# fmc_digital_io_fmc_connector.net
KiCad netlist of a schematic drawn in Altium Designer
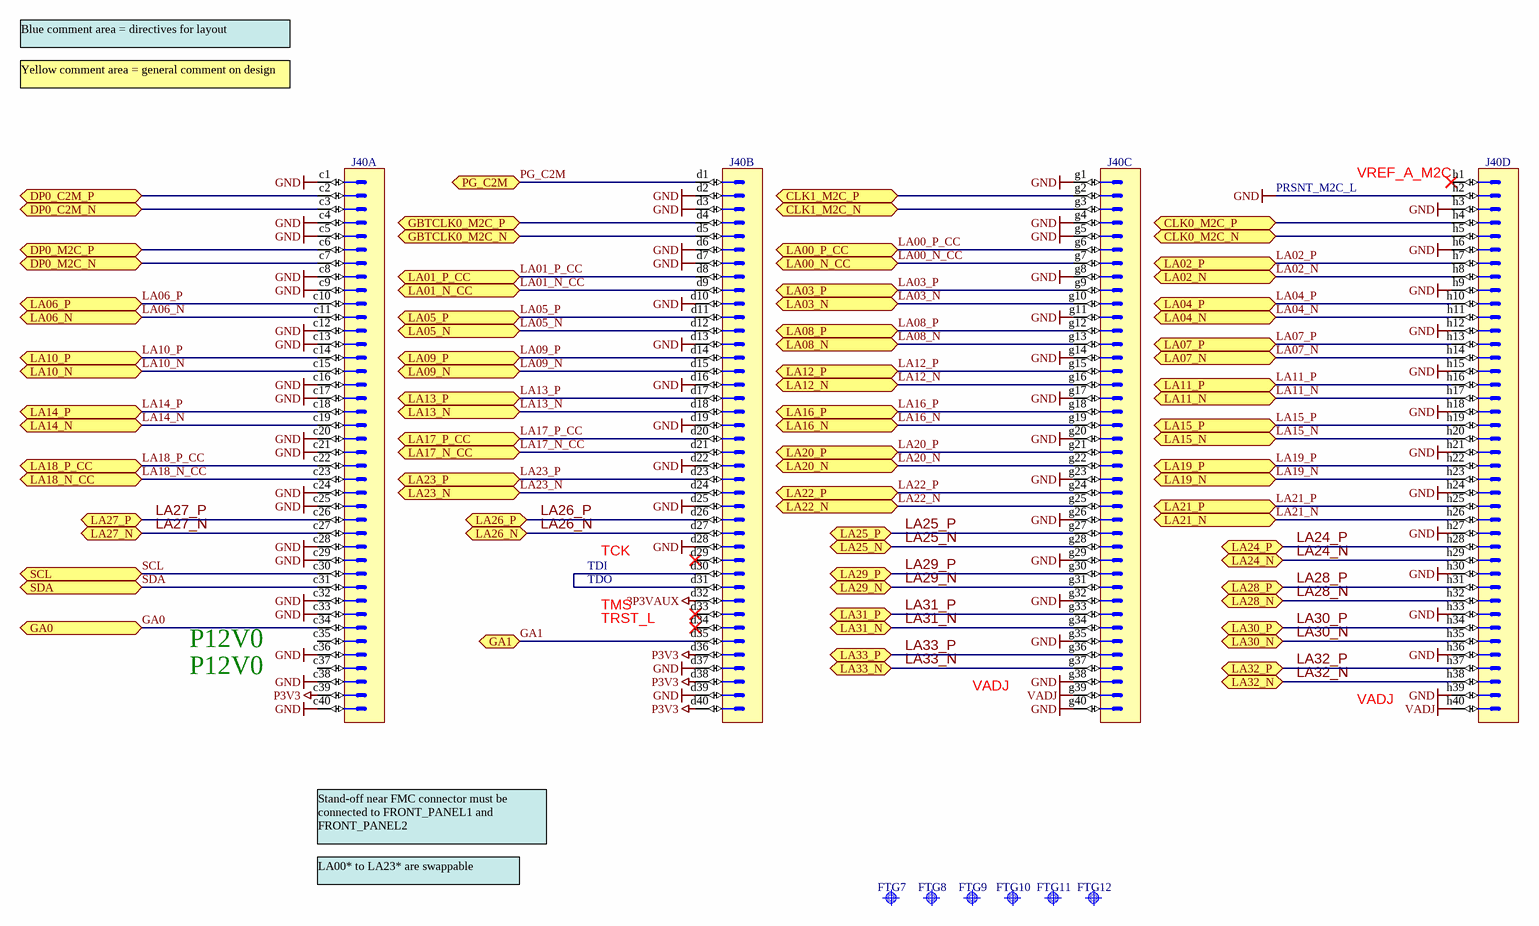
[diagram p0: fmc_digital_io_fmc_connector.SchDoc]

(export (version "E")
  (design (tool "Eeschema 10.0.6"))
  (components
    (comp (ref "FTG7")
      (value "Use only in PCB")
      (footprint "FIDUCIAL_TOP_S100-200")
      (description "Fiducial Target")
      (fields (field (name "PART NUMBER") "FIDUCIAL_TARGET_S100-200") (field (name "AUTHOR") "CERN DEM JLC"))
      (libsource (lib "Eletro-mechanical") (part "Fiducial Target"))
    )
    (comp (ref "FTG8")
      (value "Use only in PCB")
      (footprint "FIDUCIAL_TOP_S100-200")
      (description "Fiducial Target")
      (fields (field (name "PART NUMBER") "FIDUCIAL_TARGET_S100-200") (field (name "AUTHOR") "CERN DEM JLC"))
      (libsource (lib "Eletro-mechanical") (part "Fiducial Target"))
    )
    (comp (ref "FTG9")
      (value "Use only in PCB")
      (footprint "FIDUCIAL_TOP_S100-200")
      (description "Fiducial Target")
      (fields (field (name "PART NUMBER") "FIDUCIAL_TARGET_S100-200") (field (name "AUTHOR") "CERN DEM JLC"))
      (libsource (lib "Eletro-mechanical") (part "Fiducial Target"))
    )
    (comp (ref "FTG10")
      (value "Use only in PCB")
      (footprint "FIDUCIAL_TOP_S100-200")
      (description "Fiducial Target")
      (fields (field (name "PART NUMBER") "FIDUCIAL_TARGET_S100-200") (field (name "AUTHOR") "CERN DEM JLC"))
      (libsource (lib "Eletro-mechanical") (part "Fiducial Target"))
    )
    (comp (ref "FTG11")
      (value "Use only in PCB")
      (footprint "FIDUCIAL_TOP_S100-200")
      (description "Fiducial Target")
      (fields (field (name "PART NUMBER") "FIDUCIAL_TARGET_S100-200") (field (name "AUTHOR") "CERN DEM JLC"))
      (libsource (lib "Eletro-mechanical") (part "Fiducial Target"))
    )
    (comp (ref "FTG12")
      (value "Use only in PCB")
      (footprint "FIDUCIAL_TOP_S100-200")
      (description "Fiducial Target")
      (fields (field (name "PART NUMBER") "FIDUCIAL_TARGET_S100-200") (field (name "AUTHOR") "CERN DEM JLC"))
      (libsource (lib "Eletro-mechanical") (part "Fiducial Target"))
    )
    (comp (ref "J40")
      (value "VITA 57")
      (footprint "SAMTEC_ASP-127797-01")
      (description "Connector VITA 57, 160 Male contacts in 4 row cdgh")
      (fields
        (field (name "PART NUMBER") "SAMTEC_ASP-127797-01")
        (field (name "MANUFACTURER") "SAMTEC")
        (field (name "AUTHOR") "CERN DEM JLC")
      )
      (libsource (lib "Connectors") (part "Connector VITA 57 160 Male (cdgh)"))
    )
  )
  (nets
    (net (code "1") (name "/CLK0_M2C_N") (class "Default")
      (node (ref "J40") (pin "h5") (pinfunction "h5_h5") (pintype "bidirectional"))
    )
    (net (code "2") (name "/CLK0_M2C_P") (class "Default")
      (node (ref "J40") (pin "h4") (pinfunction "h4_h4") (pintype "bidirectional"))
    )
    (net (code "3") (name "/CLK1_M2C_N") (class "Default")
      (node (ref "J40") (pin "g3") (pinfunction "g3_g3") (pintype "bidirectional"))
    )
    (net (code "4") (name "/CLK1_M2C_P") (class "Default")
      (node (ref "J40") (pin "g2") (pinfunction "g2_g2") (pintype "bidirectional"))
    )
    (net (code "5") (name "/DP0_C2M_N") (class "Default")
      (node (ref "J40") (pin "c3") (pinfunction "c3_c3") (pintype "bidirectional"))
    )
    (net (code "6") (name "/DP0_C2M_P") (class "Default")
      (node (ref "J40") (pin "c2") (pinfunction "c2_c2") (pintype "bidirectional"))
    )
    (net (code "7") (name "/DP0_M2C_N") (class "Default")
      (node (ref "J40") (pin "c7") (pinfunction "c7_c7") (pintype "bidirectional"))
    )
    (net (code "8") (name "/DP0_M2C_P") (class "Default")
      (node (ref "J40") (pin "c6") (pinfunction "c6_c6") (pintype "bidirectional"))
    )
    (net (code "9") (name "/GA0") (class "Default")
      (node (ref "J40") (pin "c34") (pinfunction "c34_c34") (pintype "bidirectional"))
    )
    (net (code "10") (name "/GA1") (class "Default")
      (node (ref "J40") (pin "d35") (pinfunction "d35_d35") (pintype "bidirectional"))
    )
    (net (code "11") (name "/GBTCLK0_M2C_N") (class "Default")
      (node (ref "J40") (pin "d5") (pinfunction "d5_d5") (pintype "bidirectional"))
    )
    (net (code "12") (name "/GBTCLK0_M2C_P") (class "Default")
      (node (ref "J40") (pin "d4") (pinfunction "d4_d4") (pintype "bidirectional"))
    )
    (net (code "13") (name "/LA00_N_CC") (class "Default")
      (node (ref "J40") (pin "g7") (pinfunction "g7_g7") (pintype "bidirectional"))
    )
    (net (code "14") (name "/LA00_P_CC") (class "Default")
      (node (ref "J40") (pin "g6") (pinfunction "g6_g6") (pintype "bidirectional"))
    )
    (net (code "15") (name "/LA01_N_CC") (class "Default")
      (node (ref "J40") (pin "d9") (pinfunction "d9_d9") (pintype "bidirectional"))
    )
    (net (code "16") (name "/LA01_P_CC") (class "Default")
      (node (ref "J40") (pin "d8") (pinfunction "d8_d8") (pintype "bidirectional"))
    )
    (net (code "17") (name "/LA02_N") (class "Default")
      (node (ref "J40") (pin "h8") (pinfunction "h8_h8") (pintype "bidirectional"))
    )
    (net (code "18") (name "/LA02_P") (class "Default")
      (node (ref "J40") (pin "h7") (pinfunction "h7_h7") (pintype "bidirectional"))
    )
    (net (code "19") (name "/LA03_N") (class "Default")
      (node (ref "J40") (pin "g10") (pinfunction "g10_g10") (pintype "bidirectional"))
    )
    (net (code "20") (name "/LA03_P") (class "Default")
      (node (ref "J40") (pin "g9") (pinfunction "g9_g9") (pintype "bidirectional"))
    )
    (net (code "21") (name "/LA04_N") (class "Default")
      (node (ref "J40") (pin "h11") (pinfunction "h11_h11") (pintype "bidirectional"))
    )
    (net (code "22") (name "/LA04_P") (class "Default")
      (node (ref "J40") (pin "h10") (pinfunction "h10_h10") (pintype "bidirectional"))
    )
    (net (code "23") (name "/LA05_N") (class "Default")
      (node (ref "J40") (pin "d12") (pinfunction "d12_d12") (pintype "bidirectional"))
    )
    (net (code "24") (name "/LA05_P") (class "Default")
      (node (ref "J40") (pin "d11") (pinfunction "d11_d11") (pintype "bidirectional"))
    )
    (net (code "25") (name "/LA06_N") (class "Default")
      (node (ref "J40") (pin "c11") (pinfunction "c11_c11") (pintype "bidirectional"))
    )
    (net (code "26") (name "/LA06_P") (class "Default")
      (node (ref "J40") (pin "c10") (pinfunction "c10_c10") (pintype "bidirectional"))
    )
    (net (code "27") (name "/LA07_N") (class "Default")
      (node (ref "J40") (pin "h14") (pinfunction "h14_h14") (pintype "bidirectional"))
    )
    (net (code "28") (name "/LA07_P") (class "Default")
      (node (ref "J40") (pin "h13") (pinfunction "h13_h13") (pintype "bidirectional"))
    )
    (net (code "29") (name "/LA08_N") (class "Default")
      (node (ref "J40") (pin "g13") (pinfunction "g13_g13") (pintype "bidirectional"))
    )
    (net (code "30") (name "/LA08_P") (class "Default")
      (node (ref "J40") (pin "g12") (pinfunction "g12_g12") (pintype "bidirectional"))
    )
    (net (code "31") (name "/LA09_N") (class "Default")
      (node (ref "J40") (pin "d15") (pinfunction "d15_d15") (pintype "bidirectional"))
    )
    (net (code "32") (name "/LA09_P") (class "Default")
      (node (ref "J40") (pin "d14") (pinfunction "d14_d14") (pintype "bidirectional"))
    )
    (net (code "33") (name "/LA10_N") (class "Default")
      (node (ref "J40") (pin "c15") (pinfunction "c15_c15") (pintype "bidirectional"))
    )
    (net (code "34") (name "/LA10_P") (class "Default")
      (node (ref "J40") (pin "c14") (pinfunction "c14_c14") (pintype "bidirectional"))
    )
    (net (code "35") (name "/LA11_N") (class "Default")
      (node (ref "J40") (pin "h17") (pinfunction "h17_h17") (pintype "bidirectional"))
    )
    (net (code "36") (name "/LA11_P") (class "Default")
      (node (ref "J40") (pin "h16") (pinfunction "h16_h16") (pintype "bidirectional"))
    )
    (net (code "37") (name "/LA12_N") (class "Default")
      (node (ref "J40") (pin "g16") (pinfunction "g16_g16") (pintype "bidirectional"))
    )
    (net (code "38") (name "/LA12_P") (class "Default")
      (node (ref "J40") (pin "g15") (pinfunction "g15_g15") (pintype "bidirectional"))
    )
    (net (code "39") (name "/LA13_N") (class "Default")
      (node (ref "J40") (pin "d18") (pinfunction "d18_d18") (pintype "bidirectional"))
    )
    (net (code "40") (name "/LA13_P") (class "Default")
      (node (ref "J40") (pin "d17") (pinfunction "d17_d17") (pintype "bidirectional"))
    )
    (net (code "41") (name "/LA14_N") (class "Default")
      (node (ref "J40") (pin "c19") (pinfunction "c19_c19") (pintype "bidirectional"))
    )
    (net (code "42") (name "/LA14_P") (class "Default")
      (node (ref "J40") (pin "c18") (pinfunction "c18_c18") (pintype "bidirectional"))
    )
    (net (code "43") (name "/LA15_N") (class "Default")
      (node (ref "J40") (pin "h20") (pinfunction "h20_h20") (pintype "bidirectional"))
    )
    (net (code "44") (name "/LA15_P") (class "Default")
      (node (ref "J40") (pin "h19") (pinfunction "h19_h19") (pintype "bidirectional"))
    )
    (net (code "45") (name "/LA16_N") (class "Default")
      (node (ref "J40") (pin "g19") (pinfunction "g19_g19") (pintype "bidirectional"))
    )
    (net (code "46") (name "/LA16_P") (class "Default")
      (node (ref "J40") (pin "g18") (pinfunction "g18_g18") (pintype "bidirectional"))
    )
    (net (code "47") (name "/LA17_N_CC") (class "Default")
      (node (ref "J40") (pin "d21") (pinfunction "d21_d21") (pintype "bidirectional"))
    )
    (net (code "48") (name "/LA17_P_CC") (class "Default")
      (node (ref "J40") (pin "d20") (pinfunction "d20_d20") (pintype "bidirectional"))
    )
    (net (code "49") (name "/LA18_N_CC") (class "Default")
      (node (ref "J40") (pin "c23") (pinfunction "c23_c23") (pintype "bidirectional"))
    )
    (net (code "50") (name "/LA18_P_CC") (class "Default")
      (node (ref "J40") (pin "c22") (pinfunction "c22_c22") (pintype "bidirectional"))
    )
    (net (code "51") (name "/LA19_N") (class "Default")
      (node (ref "J40") (pin "h23") (pinfunction "h23_h23") (pintype "bidirectional"))
    )
    (net (code "52") (name "/LA19_P") (class "Default")
      (node (ref "J40") (pin "h22") (pinfunction "h22_h22") (pintype "bidirectional"))
    )
    (net (code "53") (name "/LA20_N") (class "Default")
      (node (ref "J40") (pin "g22") (pinfunction "g22_g22") (pintype "bidirectional"))
    )
    (net (code "54") (name "/LA20_P") (class "Default")
      (node (ref "J40") (pin "g21") (pinfunction "g21_g21") (pintype "bidirectional"))
    )
    (net (code "55") (name "/LA21_N") (class "Default")
      (node (ref "J40") (pin "h26") (pinfunction "h26_h26") (pintype "bidirectional"))
    )
    (net (code "56") (name "/LA21_P") (class "Default")
      (node (ref "J40") (pin "h25") (pinfunction "h25_h25") (pintype "bidirectional"))
    )
    (net (code "57") (name "/LA22_N") (class "Default")
      (node (ref "J40") (pin "g25") (pinfunction "g25_g25") (pintype "bidirectional"))
    )
    (net (code "58") (name "/LA22_P") (class "Default")
      (node (ref "J40") (pin "g24") (pinfunction "g24_g24") (pintype "bidirectional"))
    )
    (net (code "59") (name "/LA23_N") (class "Default")
      (node (ref "J40") (pin "d24") (pinfunction "d24_d24") (pintype "bidirectional"))
    )
    (net (code "60") (name "/LA23_P") (class "Default")
      (node (ref "J40") (pin "d23") (pinfunction "d23_d23") (pintype "bidirectional"))
    )
    (net (code "61") (name "/LA24_N") (class "Default")
      (node (ref "J40") (pin "h29") (pinfunction "h29_h29") (pintype "bidirectional"))
    )
    (net (code "62") (name "/LA24_P") (class "Default")
      (node (ref "J40") (pin "h28") (pinfunction "h28_h28") (pintype "bidirectional"))
    )
    (net (code "63") (name "/LA25_N") (class "Default")
      (node (ref "J40") (pin "g28") (pinfunction "g28_g28") (pintype "bidirectional"))
    )
    (net (code "64") (name "/LA25_P") (class "Default")
      (node (ref "J40") (pin "g27") (pinfunction "g27_g27") (pintype "bidirectional"))
    )
    (net (code "65") (name "/LA26_N") (class "Default")
      (node (ref "J40") (pin "d27") (pinfunction "d27_d27") (pintype "bidirectional"))
    )
    (net (code "66") (name "/LA26_P") (class "Default")
      (node (ref "J40") (pin "d26") (pinfunction "d26_d26") (pintype "bidirectional"))
    )
    (net (code "67") (name "/LA27_N") (class "Default")
      (node (ref "J40") (pin "c27") (pinfunction "c27_c27") (pintype "bidirectional"))
    )
    (net (code "68") (name "/LA27_P") (class "Default")
      (node (ref "J40") (pin "c26") (pinfunction "c26_c26") (pintype "bidirectional"))
    )
    (net (code "69") (name "/LA28_N") (class "Default")
      (node (ref "J40") (pin "h32") (pinfunction "h32_h32") (pintype "bidirectional"))
    )
    (net (code "70") (name "/LA28_P") (class "Default")
      (node (ref "J40") (pin "h31") (pinfunction "h31_h31") (pintype "bidirectional"))
    )
    (net (code "71") (name "/LA29_N") (class "Default")
      (node (ref "J40") (pin "g31") (pinfunction "g31_g31") (pintype "bidirectional"))
    )
    (net (code "72") (name "/LA29_P") (class "Default")
      (node (ref "J40") (pin "g30") (pinfunction "g30_g30") (pintype "bidirectional"))
    )
    (net (code "73") (name "/LA30_N") (class "Default")
      (node (ref "J40") (pin "h35") (pinfunction "h35_h35") (pintype "bidirectional"))
    )
    (net (code "74") (name "/LA30_P") (class "Default")
      (node (ref "J40") (pin "h34") (pinfunction "h34_h34") (pintype "bidirectional"))
    )
    (net (code "75") (name "/LA31_N") (class "Default")
      (node (ref "J40") (pin "g34") (pinfunction "g34_g34") (pintype "bidirectional"))
    )
    (net (code "76") (name "/LA31_P") (class "Default")
      (node (ref "J40") (pin "g33") (pinfunction "g33_g33") (pintype "bidirectional"))
    )
    (net (code "77") (name "/LA32_N") (class "Default")
      (node (ref "J40") (pin "h38") (pinfunction "h38_h38") (pintype "bidirectional"))
    )
    (net (code "78") (name "/LA32_P") (class "Default")
      (node (ref "J40") (pin "h37") (pinfunction "h37_h37") (pintype "bidirectional"))
    )
    (net (code "79") (name "/LA33_N") (class "Default")
      (node (ref "J40") (pin "g37") (pinfunction "g37_g37") (pintype "bidirectional"))
    )
    (net (code "80") (name "/LA33_P") (class "Default")
      (node (ref "J40") (pin "g36") (pinfunction "g36_g36") (pintype "bidirectional"))
    )
    (net (code "81") (name "/PG_C2M") (class "Default")
      (node (ref "J40") (pin "d1") (pinfunction "d1_d1") (pintype "bidirectional"))
    )
    (net (code "82") (name "/SCL") (class "Default")
      (node (ref "J40") (pin "c30") (pinfunction "c30_c30") (pintype "bidirectional"))
    )
    (net (code "83") (name "/SDA") (class "Default")
      (node (ref "J40") (pin "c31") (pinfunction "c31_c31") (pintype "bidirectional"))
    )
    (net (code "84") (name "3P3VAUX") (class "Default")
      (node (ref "J40") (pin "d32") (pinfunction "d32_d32") (pintype "bidirectional"))
    )
    (net (code "85") (name "GND") (class "Default")
      (node (ref "J40") (pin "c1") (pinfunction "c1_c1") (pintype "bidirectional"))
      (node (ref "J40") (pin "c12") (pinfunction "c12_c12") (pintype "bidirectional"))
      (node (ref "J40") (pin "c13") (pinfunction "c13_c13") (pintype "bidirectional"))
      (node (ref "J40") (pin "c16") (pinfunction "c16_c16") (pintype "bidirectional"))
      (node (ref "J40") (pin "c17") (pinfunction "c17_c17") (pintype "bidirectional"))
      (node (ref "J40") (pin "c20") (pinfunction "c20_c20") (pintype "bidirectional"))
      (node (ref "J40") (pin "c21") (pinfunction "c21_c21") (pintype "bidirectional"))
      (node (ref "J40") (pin "c24") (pinfunction "c24_c24") (pintype "bidirectional"))
      (node (ref "J40") (pin "c25") (pinfunction "c25_c25") (pintype "bidirectional"))
      (node (ref "J40") (pin "c28") (pinfunction "c28_c28") (pintype "bidirectional"))
      (node (ref "J40") (pin "c29") (pinfunction "c29_c29") (pintype "bidirectional"))
      (node (ref "J40") (pin "c32") (pinfunction "c32_c32") (pintype "bidirectional"))
      (node (ref "J40") (pin "c33") (pinfunction "c33_c33") (pintype "bidirectional"))
      (node (ref "J40") (pin "c36") (pinfunction "c36_c36") (pintype "bidirectional"))
      (node (ref "J40") (pin "c38") (pinfunction "c38_c38") (pintype "bidirectional"))
      (node (ref "J40") (pin "c4") (pinfunction "c4_c4") (pintype "bidirectional"))
      (node (ref "J40") (pin "c40") (pinfunction "c40_c40") (pintype "bidirectional"))
      (node (ref "J40") (pin "c5") (pinfunction "c5_c5") (pintype "bidirectional"))
      (node (ref "J40") (pin "c8") (pinfunction "c8_c8") (pintype "bidirectional"))
      (node (ref "J40") (pin "c9") (pinfunction "c9_c9") (pintype "bidirectional"))
      (node (ref "J40") (pin "d10") (pinfunction "d10_d10") (pintype "bidirectional"))
      (node (ref "J40") (pin "d13") (pinfunction "d13_d13") (pintype "bidirectional"))
      (node (ref "J40") (pin "d16") (pinfunction "d16_d16") (pintype "bidirectional"))
      (node (ref "J40") (pin "d19") (pinfunction "d19_d19") (pintype "bidirectional"))
      (node (ref "J40") (pin "d2") (pinfunction "d2_d2") (pintype "bidirectional"))
      (node (ref "J40") (pin "d22") (pinfunction "d22_d22") (pintype "bidirectional"))
      (node (ref "J40") (pin "d25") (pinfunction "d25_d25") (pintype "bidirectional"))
      (node (ref "J40") (pin "d28") (pinfunction "d28_d28") (pintype "bidirectional"))
      (node (ref "J40") (pin "d3") (pinfunction "d3_d3") (pintype "bidirectional"))
      (node (ref "J40") (pin "d37") (pinfunction "d37_d37") (pintype "bidirectional"))
      (node (ref "J40") (pin "d39") (pinfunction "d39_d39") (pintype "bidirectional"))
      (node (ref "J40") (pin "d6") (pinfunction "d6_d6") (pintype "bidirectional"))
      (node (ref "J40") (pin "d7") (pinfunction "d7_d7") (pintype "bidirectional"))
      (node (ref "J40") (pin "g1") (pinfunction "g1_g1") (pintype "bidirectional"))
      (node (ref "J40") (pin "g11") (pinfunction "g11_g11") (pintype "bidirectional"))
      (node (ref "J40") (pin "g14") (pinfunction "g14_g14") (pintype "bidirectional"))
      (node (ref "J40") (pin "g17") (pinfunction "g17_g17") (pintype "bidirectional"))
      (node (ref "J40") (pin "g20") (pinfunction "g20_g20") (pintype "bidirectional"))
      (node (ref "J40") (pin "g23") (pinfunction "g23_g23") (pintype "bidirectional"))
      (node (ref "J40") (pin "g26") (pinfunction "g26_g26") (pintype "bidirectional"))
      (node (ref "J40") (pin "g29") (pinfunction "g29_g29") (pintype "bidirectional"))
      (node (ref "J40") (pin "g32") (pinfunction "g32_g32") (pintype "bidirectional"))
      (node (ref "J40") (pin "g35") (pinfunction "g35_g35") (pintype "bidirectional"))
      (node (ref "J40") (pin "g38") (pinfunction "g38_g38") (pintype "bidirectional"))
      (node (ref "J40") (pin "g4") (pinfunction "g4_g4") (pintype "bidirectional"))
      (node (ref "J40") (pin "g40") (pinfunction "g40_g40") (pintype "bidirectional"))
      (node (ref "J40") (pin "g5") (pinfunction "g5_g5") (pintype "bidirectional"))
      (node (ref "J40") (pin "g8") (pinfunction "g8_g8") (pintype "bidirectional"))
      (node (ref "J40") (pin "h12") (pinfunction "h12_h12") (pintype "bidirectional"))
      (node (ref "J40") (pin "h15") (pinfunction "h15_h15") (pintype "bidirectional"))
      (node (ref "J40") (pin "h18") (pinfunction "h18_h18") (pintype "bidirectional"))
      (node (ref "J40") (pin "h2") (pinfunction "h2_h2") (pintype "bidirectional"))
      (node (ref "J40") (pin "h21") (pinfunction "h21_h21") (pintype "bidirectional"))
      (node (ref "J40") (pin "h24") (pinfunction "h24_h24") (pintype "bidirectional"))
      (node (ref "J40") (pin "h27") (pinfunction "h27_h27") (pintype "bidirectional"))
      (node (ref "J40") (pin "h3") (pinfunction "h3_h3") (pintype "bidirectional"))
      (node (ref "J40") (pin "h30") (pinfunction "h30_h30") (pintype "bidirectional"))
      (node (ref "J40") (pin "h33") (pinfunction "h33_h33") (pintype "bidirectional"))
      (node (ref "J40") (pin "h36") (pinfunction "h36_h36") (pintype "bidirectional"))
      (node (ref "J40") (pin "h39") (pinfunction "h39_h39") (pintype "bidirectional"))
      (node (ref "J40") (pin "h6") (pinfunction "h6_h6") (pintype "bidirectional"))
      (node (ref "J40") (pin "h9") (pinfunction "h9_h9") (pintype "bidirectional"))
    )
    (net (code "86") (name "Net-(J40-Padd30)") (class "Default")
      (node (ref "J40") (pin "d30") (pinfunction "d30_d30") (pintype "bidirectional"))
      (node (ref "J40") (pin "d31") (pinfunction "d31_d31") (pintype "bidirectional"))
    )
    (net (code "87") (name "P3V3") (class "Default")
      (node (ref "J40") (pin "c39") (pinfunction "c39_c39") (pintype "bidirectional"))
      (node (ref "J40") (pin "d36") (pinfunction "d36_d36") (pintype "bidirectional"))
      (node (ref "J40") (pin "d38") (pinfunction "d38_d38") (pintype "bidirectional"))
      (node (ref "J40") (pin "d40") (pinfunction "d40_d40") (pintype "bidirectional"))
    )
    (net (code "88") (name "VADJ") (class "Default")
      (node (ref "J40") (pin "g39") (pinfunction "g39_g39") (pintype "bidirectional"))
      (node (ref "J40") (pin "h40") (pinfunction "h40_h40") (pintype "bidirectional"))
    )
    (net (code "89") (name "unconnected-(J40-Padc35)") (class "Default")
      (node (ref "J40") (pin "c35") (pinfunction "c35_c35") (pintype "bidirectional"))
    )
    (net (code "90") (name "unconnected-(J40-Padc37)") (class "Default")
      (node (ref "J40") (pin "c37") (pinfunction "c37_c37") (pintype "bidirectional"))
    )
    (net (code "91") (name "unconnected-(J40-Padd29)") (class "Default")
      (node (ref "J40") (pin "d29") (pinfunction "d29_d29") (pintype "bidirectional+no_connect"))
    )
    (net (code "92") (name "unconnected-(J40-Padd33)") (class "Default")
      (node (ref "J40") (pin "d33") (pinfunction "d33_d33") (pintype "bidirectional+no_connect"))
    )
    (net (code "93") (name "unconnected-(J40-Padd34)") (class "Default")
      (node (ref "J40") (pin "d34") (pinfunction "d34_d34") (pintype "bidirectional+no_connect"))
    )
    (net (code "94") (name "unconnected-(J40-Padh1)") (class "Default")
      (node (ref "J40") (pin "h1") (pinfunction "h1_h1") (pintype "bidirectional+no_connect"))
    )
  )
)
